# boardv2temperature.net
KiCad netlist of a schematic drawn in EAGLE
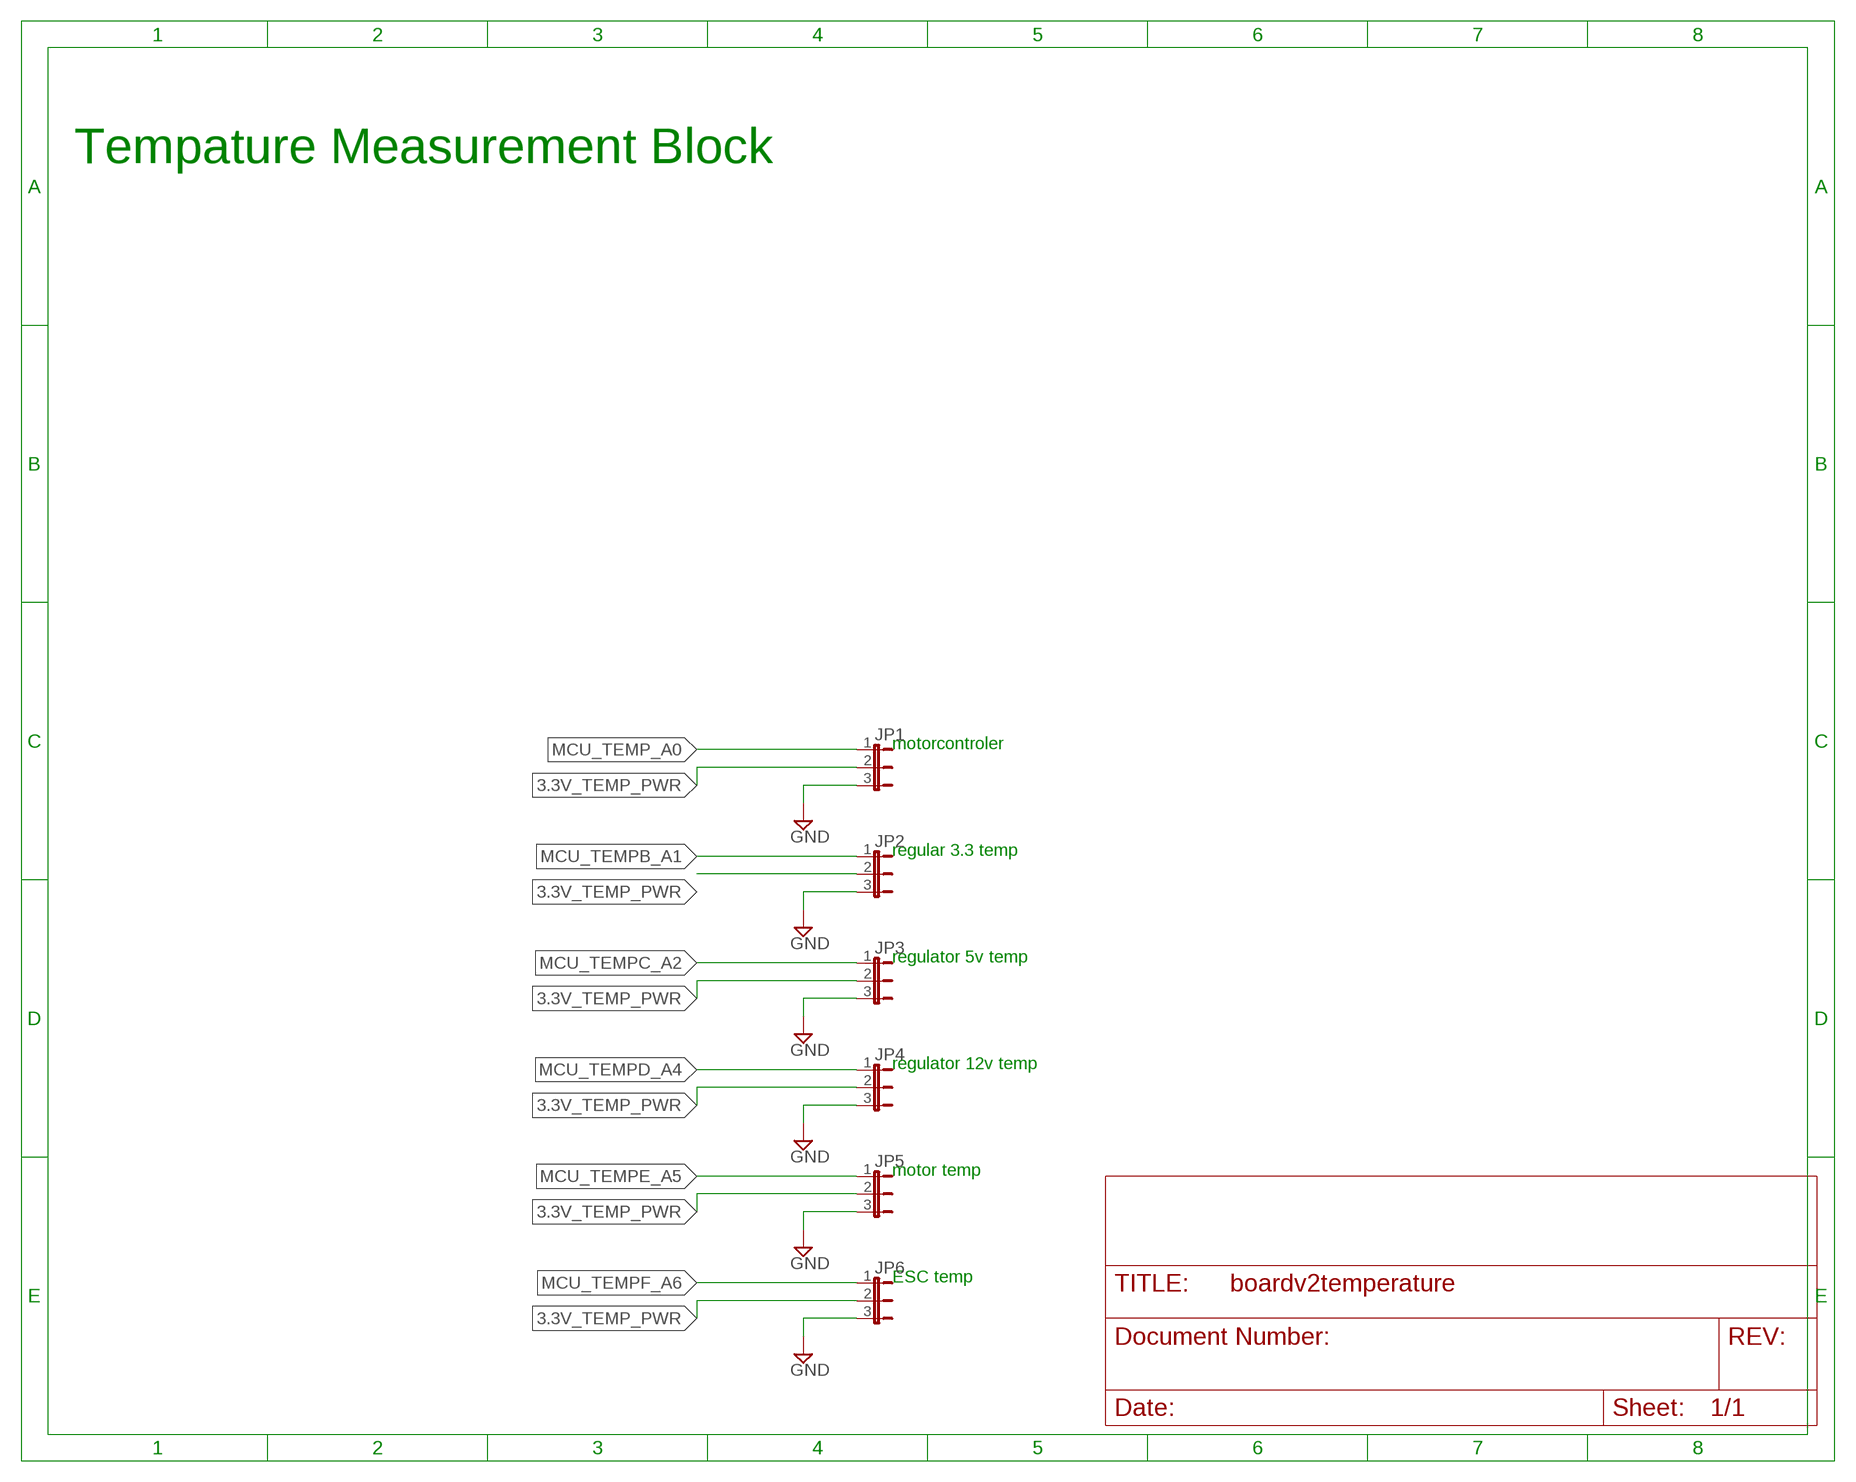
[diagram p0: schematic, sheet 1]

(export (version "E")
  (design (tool "Eeschema 10.0.6"))
  (components
    (comp (ref "JP1")
      (value "JP2E")
      (footprint "eagle-import:JP2")
      (libsource (lib "eagle-import") (part "JP2E"))
    )
    (comp (ref "JP2")
      (value "JP2E")
      (footprint "eagle-import:JP2")
      (libsource (lib "eagle-import") (part "JP2E"))
    )
    (comp (ref "JP3")
      (value "JP2E")
      (footprint "eagle-import:JP2")
      (libsource (lib "eagle-import") (part "JP2E"))
    )
    (comp (ref "JP4")
      (value "JP2E")
      (footprint "eagle-import:JP2")
      (libsource (lib "eagle-import") (part "JP2E"))
    )
    (comp (ref "JP5")
      (value "JP2E")
      (footprint "eagle-import:JP2")
      (libsource (lib "eagle-import") (part "JP2E"))
    )
    (comp (ref "JP6")
      (value "JP2E")
      (footprint "eagle-import:JP2")
      (libsource (lib "eagle-import") (part "JP2E"))
    )
  )
  (nets
    (net (code "1") (name "3.3V_TEMP_PWR") (class "Default")
      (node (ref "JP1") (pin "2") (pinfunction "2_2") (pintype "passive"))
      (node (ref "JP2") (pin "2") (pinfunction "2_2") (pintype "passive"))
      (node (ref "JP3") (pin "2") (pinfunction "2_2") (pintype "passive"))
      (node (ref "JP4") (pin "2") (pinfunction "2_2") (pintype "passive"))
      (node (ref "JP5") (pin "2") (pinfunction "2_2") (pintype "passive"))
      (node (ref "JP6") (pin "2") (pinfunction "2_2") (pintype "passive"))
    )
    (net (code "2") (name "GND") (class "Default")
      (node (ref "JP1") (pin "3") (pinfunction "3_3") (pintype "passive"))
      (node (ref "JP2") (pin "3") (pinfunction "3_3") (pintype "passive"))
      (node (ref "JP3") (pin "3") (pinfunction "3_3") (pintype "passive"))
      (node (ref "JP4") (pin "3") (pinfunction "3_3") (pintype "passive"))
      (node (ref "JP5") (pin "3") (pinfunction "3_3") (pintype "passive"))
      (node (ref "JP6") (pin "3") (pinfunction "3_3") (pintype "passive"))
    )
    (net (code "3") (name "MCU_TEMPB_A1") (class "Default")
      (node (ref "JP2") (pin "1") (pinfunction "1_1") (pintype "passive"))
    )
    (net (code "4") (name "MCU_TEMPC_A2") (class "Default")
      (node (ref "JP3") (pin "1") (pinfunction "1_1") (pintype "passive"))
    )
    (net (code "5") (name "MCU_TEMPD_A4") (class "Default")
      (node (ref "JP4") (pin "1") (pinfunction "1_1") (pintype "passive"))
    )
    (net (code "6") (name "MCU_TEMPE_A5") (class "Default")
      (node (ref "JP5") (pin "1") (pinfunction "1_1") (pintype "passive"))
    )
    (net (code "7") (name "MCU_TEMPF_A6") (class "Default")
      (node (ref "JP6") (pin "1") (pinfunction "1_1") (pintype "passive"))
    )
    (net (code "8") (name "MCU_TEMP_A0") (class "Default")
      (node (ref "JP1") (pin "1") (pinfunction "1_1") (pintype "passive"))
    )
  )
)
